# Vapeix_mini_power.net
KiCad netlist of a schematic drawn in Altium Designer
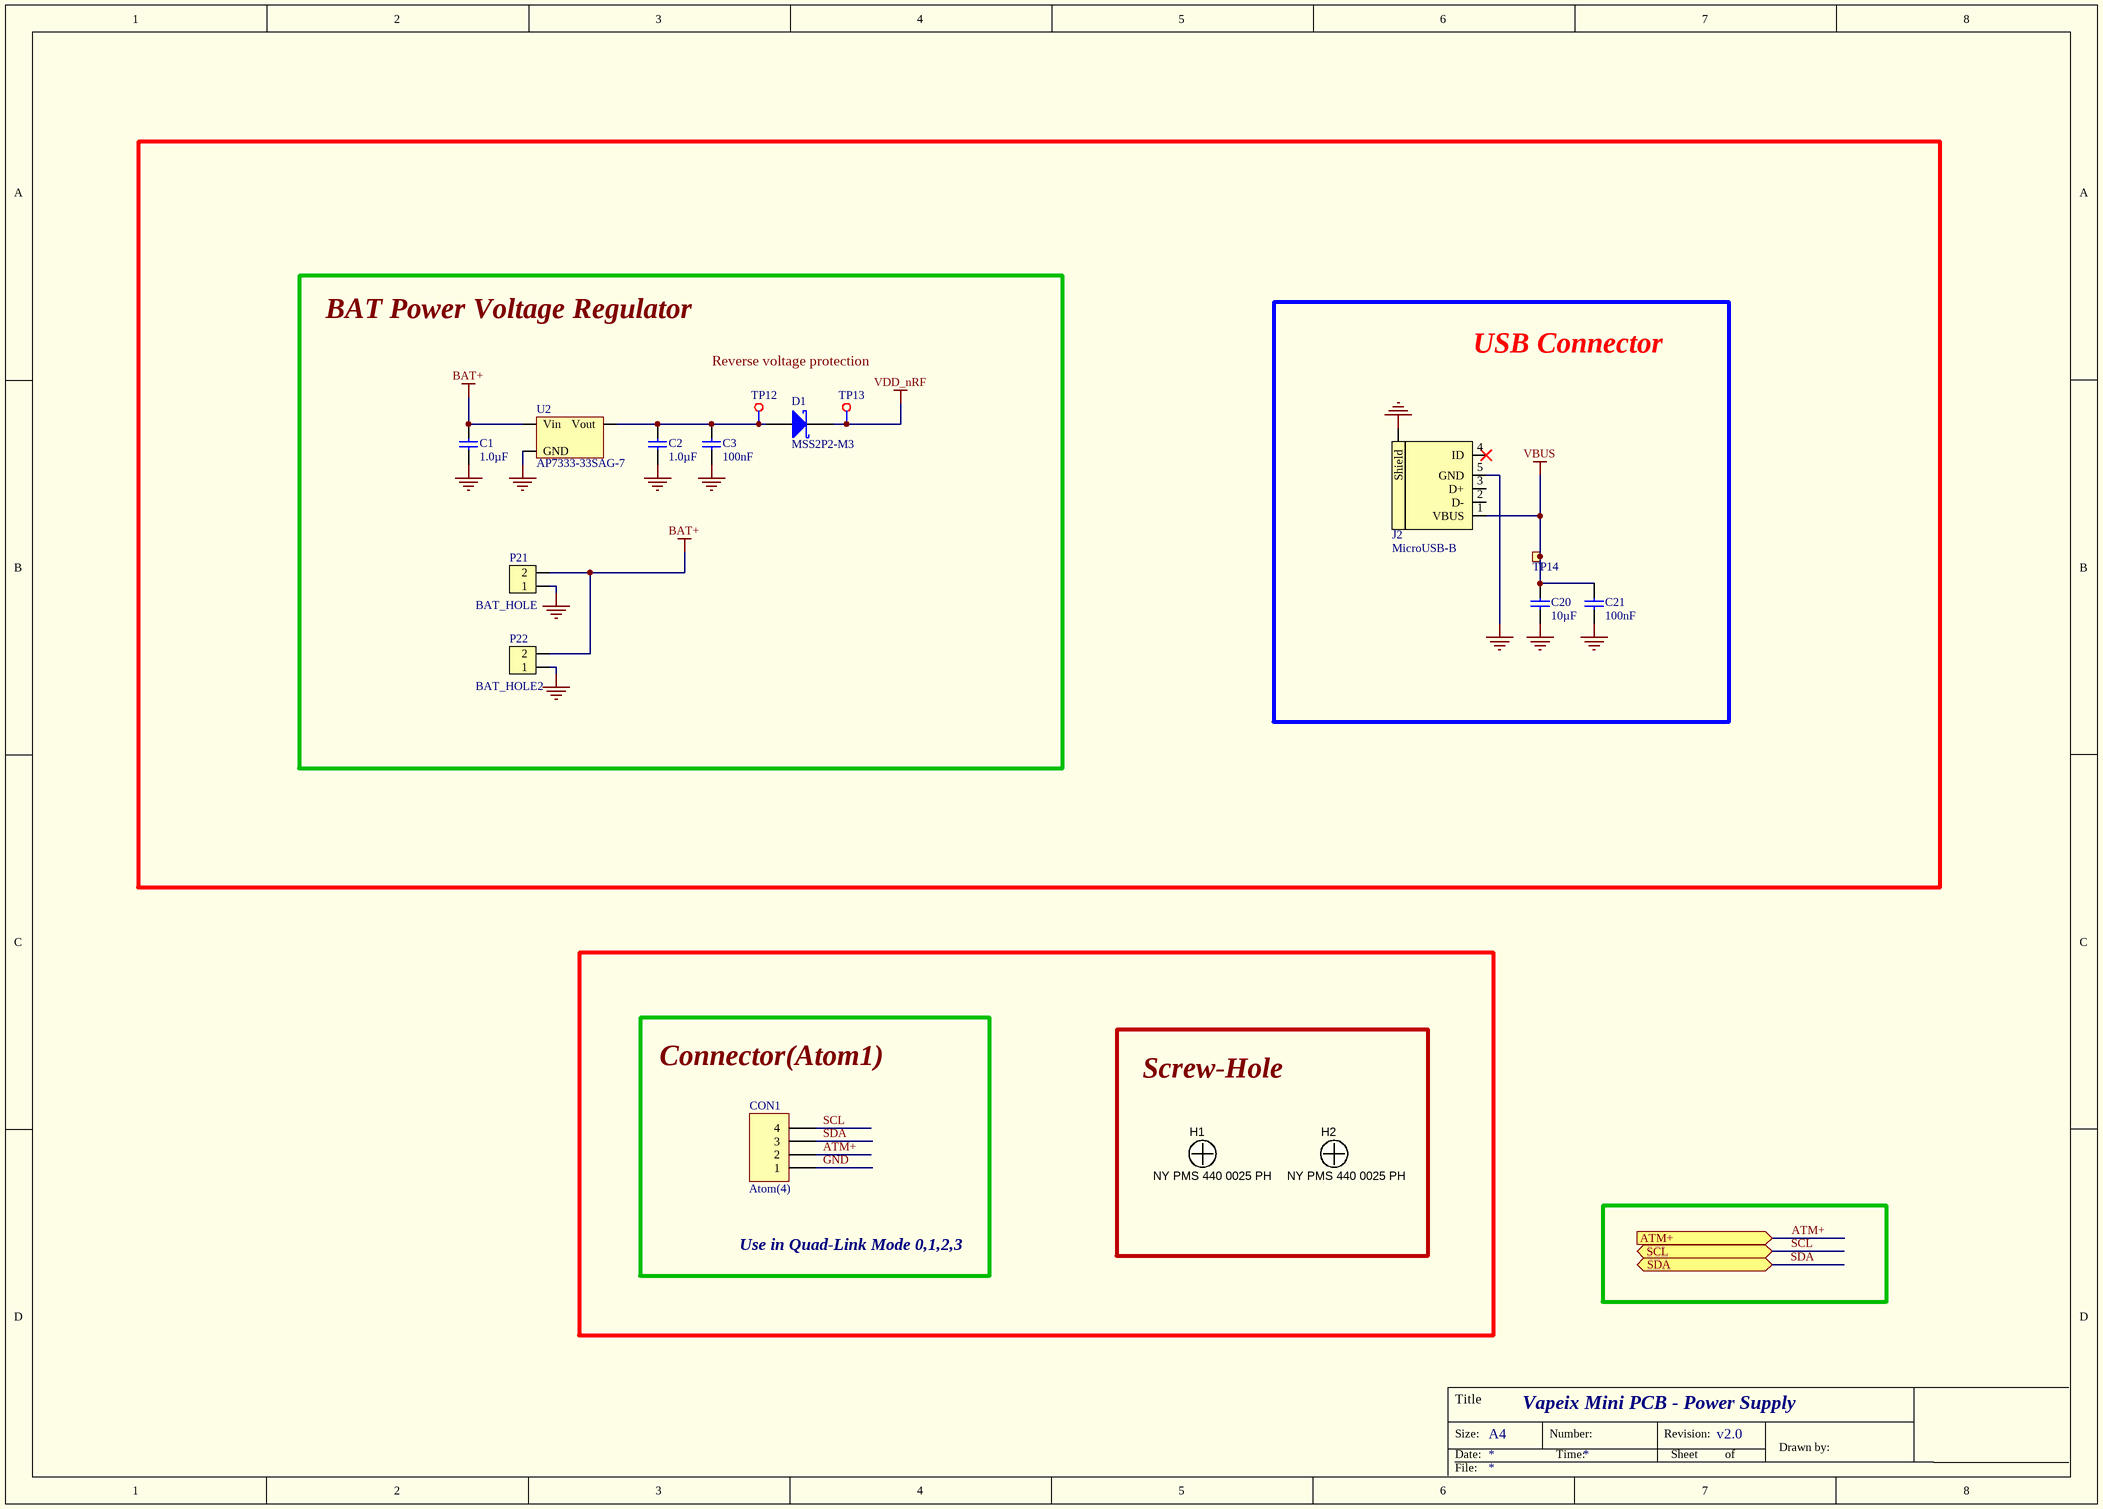
[diagram p0: Vapeix_mini_power.SchDoc]

(export (version "E")
  (design (tool "Eeschema 10.0.6"))
  (components
    (comp (ref "C1")
      (value "1.0µF")
      (footprint "C0201")
      (description "CAP CER 1UF 16V X5R 0201")
      (fields
        (field (name "MANUFACTURER") "Samsung Electro-Mechanics America, Inc.")
        (field (name "MANUFACTURER PART NUMBER") "CL03A105MO3NRNH")
      )
      (libsource (lib "Nordic Passive DB") (part "CAP"))
    )
    (comp (ref "C2")
      (value "1.0µF")
      (footprint "C0201")
      (description "CAP CER 1UF 16V X5R 0201")
      (fields
        (field (name "MANUFACTURER") "Samsung Electro-Mechanics America, Inc.")
        (field (name "MANUFACTURER PART NUMBER") "CL03A105MO3NRNH")
      )
      (libsource (lib "Nordic Passive DB") (part "CAP"))
    )
    (comp (ref "C3")
      (value "100nF")
      (footprint "C0201")
      (description "CAP CER 0.1UF 10V X5R 0201")
      (fields
        (field (name "PART NUMBER") "C0402-100n")
        (field (name "MANUFACTURER") "Murata Electronics North America")
        (field (name "PUBLISHER") "Nordic Semiconductor")
      )
      (libsource (lib "Nordic Passive DB") (part "CAP"))
    )
    (comp (ref "C20")
      (value "10µF")
      (footprint "R0402")
      (description "CAP CER 10UF 10V X5R 0402")
      (fields
        (field (name "MANUFACTURER") "Samsung Electro-Mechanics America, Inc.")
        (field (name "MANUFACTURER PART NUMBER") "CL05A106MP5NUNC")
        (field (name "PUBLISHER") "Nordic Semiconductor")
      )
      (libsource (lib "Nordic Passive DB") (part "CAP"))
    )
    (comp (ref "C21")
      (value "100nF")
      (footprint "C0201")
      (description "CAP CER 0.1UF 10V X5R 0201")
      (fields
        (field (name "PART NUMBER") "C0402-100n")
        (field (name "MANUFACTURER") "Murata Electronics North America")
        (field (name "PUBLISHER") "Nordic Semiconductor")
      )
      (libsource (lib "Nordic Passive DB") (part "CAP"))
    )
    (comp (ref "CON1")
      (value "Atom(4)")
      (footprint "S4B-PH-K-S")
      (description "CONN HEADER PH SIDE 4POS 2MM")
      (fields
        (field (name "MANUFACTURER") "JST Sales America Inc.")
        (field (name "MANUFACTURER PART NUMBER") "S4B-PH-K-S(LF)(SN)")
      )
      (libsource (lib "VapeixS_LIB") (part "S4B-PH-K-S(LF)(SN)"))
    )
    (comp (ref "D1")
      (value "MSS2P2-M3")
      (footprint "MSS2P2-M3")
      (description "DIODE SCHOTTKY 20V 2A MICROSMP")
      (fields
        (field (name "MANUFACTURER") "Vishay Semiconductor Diodes Division")
        (field (name "MANUFACTURER PART NUMBER") "MSS2P2-M3/89A")
      )
      (libsource (lib "VapeixS_LIB") (part "MSS2P2-M3/89A"))
    )
    (comp (ref "H1")
      (value "NY PMS 440 0025 PH")
      (footprint "SCREW_HOLE2")
      (description "Machine Screw, Round, #4-40 x 1/4, Nylon, Philips panhead")
      (fields
        (field (name "MANUFACTURER") "B&F Fastener Supply")
        (field (name "DIGIKEYPARTNUMBER") "H542-ND")
        (field (name "SYMBOLCREATOR") "codlsc")
        (field (name "PUBLISHER") "Texas Instruments")
      )
      (libsource (lib "VapeixS_LIB") (part "Screw-Hole"))
    )
    (comp (ref "H2")
      (value "NY PMS 440 0025 PH")
      (footprint "SCREW_HOLE2")
      (description "Machine Screw, Round, #4-40 x 1/4, Nylon, Philips panhead")
      (fields
        (field (name "MANUFACTURER") "B&F Fastener Supply")
        (field (name "DIGIKEYPARTNUMBER") "H542-ND")
        (field (name "SYMBOLCREATOR") "codlsc")
        (field (name "PUBLISHER") "Texas Instruments")
      )
      (libsource (lib "VapeixS_LIB") (part "Screw-Hole"))
    )
    (comp (ref "J2")
      (value "MicroUSB-B")
      (footprint "FCI_10118193-0001LF")
      (description "MicroUSB-B-SMT")
      (fields
        (field (name "PART NUMBER") "FCI 10118193-0001LF")
        (field (name "MANUFACTURER") "FCI")
        (field (name "PUBLISHER") "Nordic Semiconductor")
      )
      (libsource (lib "Nordic Passive DB") (part "MiniUSB-AB-SMT"))
    )
    (comp (ref "P21")
      (value "BAT_HOLE")
      (footprint "CON2")
      (description "Pin List 1x2, 2.54mm (100mil), Right Angled, SMD")
      (fields
        (field (name "PART NUMBER") "Pin List Ang 1x2 SMD, 2.54mm")
        (field (name "2ND SOURCE PART NUMBER") "S1113E-02-ND")
        (field (name "PUBLISHER") "Nordic Semiconductor")
      )
      (libsource (lib "Nordic Passive DB") (part "CONN-2"))
    )
    (comp (ref "P22")
      (value "BAT_HOLE2")
      (footprint "CON2")
      (description "Pin List 1x2, 2.54mm (100mil), Right Angled, SMD")
      (fields
        (field (name "PART NUMBER") "Pin List Ang 1x2 SMD, 2.54mm")
        (field (name "2ND SOURCE PART NUMBER") "S1113E-02-ND")
        (field (name "PUBLISHER") "Nordic Semiconductor")
      )
      (libsource (lib "Nordic Passive DB") (part "CONN-2"))
    )
    (comp (ref "TP12")
      (value "TP")
      (footprint "TP")
      (description "TEST POINT")
      (libsource (lib "VapeixS_LIB") (part "TP"))
    )
    (comp (ref "TP13")
      (value "TP")
      (footprint "TP")
      (description "TEST POINT")
      (libsource (lib "VapeixS_LIB") (part "TP"))
    )
    (comp (ref "TP14")
      (value "Ø1.0mm,SMD")
      (footprint "TP_SMD_1.0mm")
      (description "1.0mm circular SMD testpad")
      (fields
        (field (name "PART NUMBER") "TP_SMD_Ø1.0MM")
        (field (name "MANUFACTURER") "Nordic Semiconductor")
        (field (name "PUBLISHER") "Nordic Semiconductor")
      )
      (libsource (lib "Vapeix") (part "TESTPAD"))
    )
    (comp (ref "U2")
      (value "AP7333-33SAG-7")
      (footprint "SOT-23A")
      (description "300mA, Low Quiescent Current, Fast Transient Low Dropout Linear Regulator")
      (fields
        (field (name "MANUFACTURER") "Diodes Incorporated")
        (field (name "PUBLISHER") "Nordic Semiconductor")
      )
      (libsource (lib "Nordic Active DB") (part "AP7333-XXSAG"))
    )
  )
  (nets
    (net (code "1") (name "/ATM+") (class "Default")
      (node (ref "CON1") (pin "2") (pinfunction "2_2") (pintype "passive"))
    )
    (net (code "4") (name "/SCL") (class "Default")
      (node (ref "CON1") (pin "4") (pinfunction "4_4") (pintype "passive"))
    )
    (net (code "5") (name "/SDA") (class "Default")
      (node (ref "CON1") (pin "3") (pinfunction "3_3") (pintype "passive"))
    )
    (net (code "9") (name "BAT+") (class "Default")
      (node (ref "C1") (pin "2") (pinfunction "2_2") (pintype "passive"))
      (node (ref "P21") (pin "2") (pinfunction "2_2") (pintype "passive"))
      (node (ref "P22") (pin "2") (pinfunction "2_2") (pintype "passive"))
      (node (ref "U2") (pin "1") (pinfunction "Vin_1") (pintype "passive"))
    )
    (net (code "10") (name "GND") (class "Default")
      (node (ref "C1") (pin "1") (pinfunction "1_1") (pintype "passive"))
      (node (ref "C2") (pin "1") (pinfunction "1_1") (pintype "passive"))
      (node (ref "C20") (pin "1") (pinfunction "1_1") (pintype "passive"))
      (node (ref "C21") (pin "2") (pinfunction "2_2") (pintype "passive"))
      (node (ref "C3") (pin "2") (pinfunction "2_2") (pintype "passive"))
      (node (ref "CON1") (pin "1") (pinfunction "1_1") (pintype "passive"))
      (node (ref "J2") (pin "5") (pinfunction "GND_5") (pintype "power_in"))
      (node (ref "J2") (pin "6") (pinfunction "Shield_6") (pintype "power_in"))
      (node (ref "P21") (pin "1") (pinfunction "1_1") (pintype "passive"))
      (node (ref "P22") (pin "1") (pinfunction "1_1") (pintype "passive"))
      (node (ref "U2") (pin "3") (pinfunction "GND_3") (pintype "passive"))
    )
    (net (code "11") (name "Net-(D1-A)") (class "Default")
      (node (ref "C2") (pin "2") (pinfunction "2_2") (pintype "passive"))
      (node (ref "C3") (pin "1") (pinfunction "1_1") (pintype "passive"))
      (node (ref "D1") (pin "1") (pinfunction "A_1") (pintype "passive"))
      (node (ref "TP12") (pin "1") (pinfunction "TP_1") (pintype "passive"))
      (node (ref "U2") (pin "2") (pinfunction "Vout_2") (pintype "passive"))
    )
    (net (code "12") (name "VBUS") (class "Default")
      (node (ref "C20") (pin "2") (pinfunction "2_2") (pintype "passive"))
      (node (ref "C21") (pin "1") (pinfunction "1_1") (pintype "passive"))
      (node (ref "J2") (pin "1") (pinfunction "VBUS_1") (pintype "power_in"))
      (node (ref "TP14") (pin "1") (pinfunction "1_1") (pintype "passive"))
    )
    (net (code "13") (name "VDD_nRF") (class "Default")
      (node (ref "D1") (pin "2") (pinfunction "K_2") (pintype "passive"))
      (node (ref "TP13") (pin "1") (pinfunction "TP_1") (pintype "passive"))
    )
    (net (code "14") (name "unconnected-(J2-D+-Pad3)") (class "Default")
      (node (ref "J2") (pin "3") (pinfunction "D+_3") (pintype "passive"))
    )
    (net (code "15") (name "unconnected-(J2-D--Pad2)") (class "Default")
      (node (ref "J2") (pin "2") (pinfunction "D-_2") (pintype "passive"))
    )
    (net (code "16") (name "unconnected-(J2-ID-Pad4)") (class "Default")
      (node (ref "J2") (pin "4") (pinfunction "ID_4") (pintype "passive+no_connect"))
    )
  )
)
